# LED_POWER.net
KiCad netlist of a schematic drawn in Altium Designer
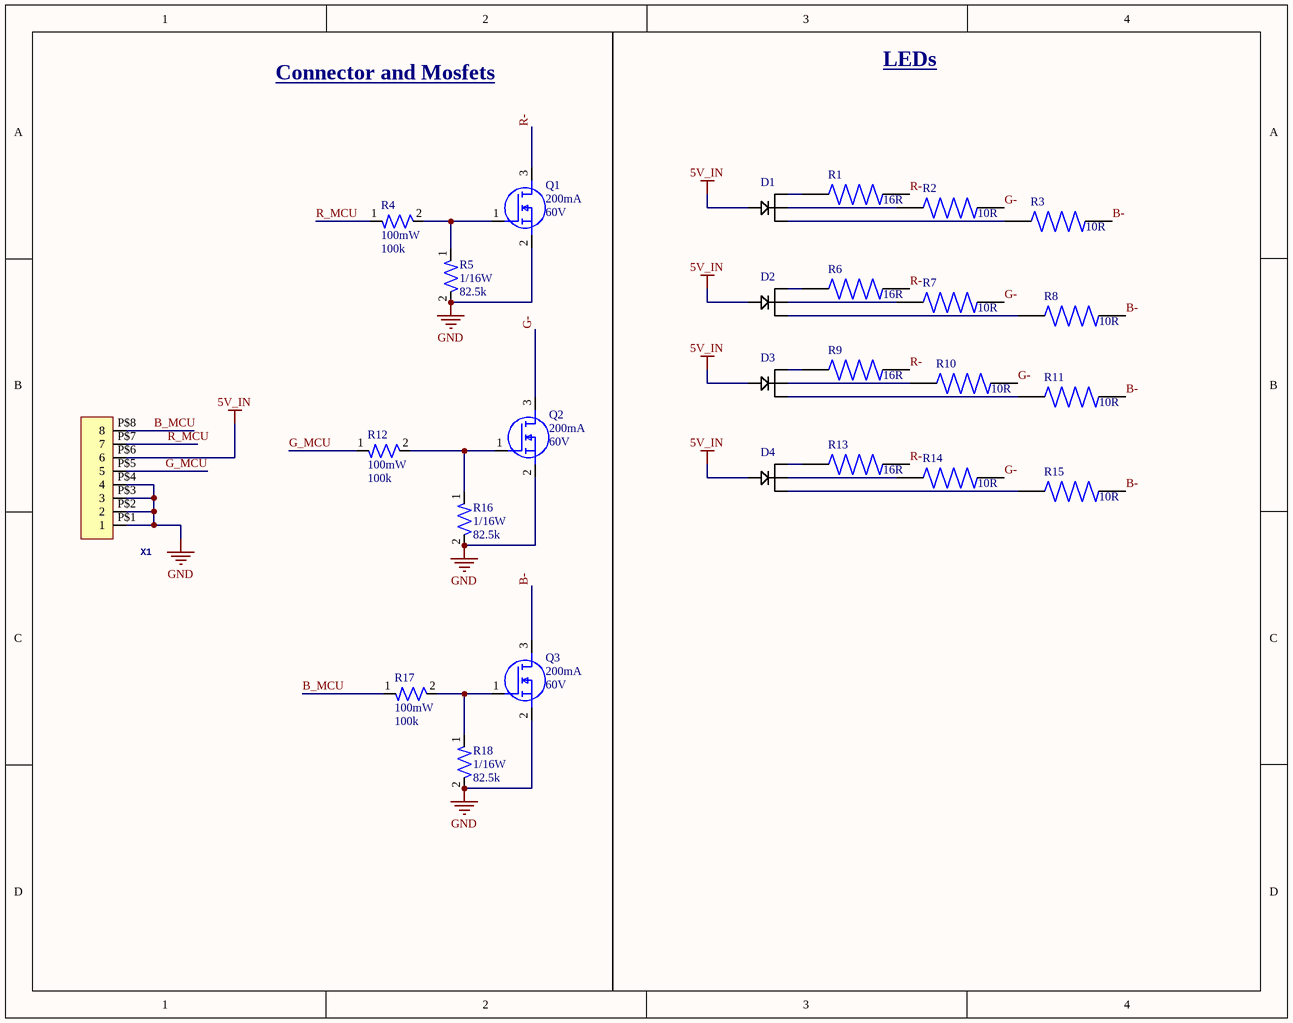
[diagram p0: LED_POWER.SchDoc]

(export (version "E")
  (design (tool "Eeschema 10.0.6"))
  (components
    (comp (ref "D1")
      (value "FD-9RGB-Y2")
      (footprint "RGBLED pcb")
      (description "https://www.adafruit.com/product/2524#technical-details")
      (libsource (lib "JLC_25") (part "3W-9W RGB LED"))
    )
    (comp (ref "D2")
      (value "FD-9RGB-Y2")
      (footprint "RGBLED pcb")
      (description "https://www.adafruit.com/product/2524#technical-details")
      (libsource (lib "JLC_25") (part "3W-9W RGB LED"))
    )
    (comp (ref "D3")
      (value "FD-9RGB-Y2")
      (footprint "RGBLED pcb")
      (description "https://www.adafruit.com/product/2524#technical-details")
      (libsource (lib "JLC_25") (part "3W-9W RGB LED"))
    )
    (comp (ref "D4")
      (value "FD-9RGB-Y2")
      (footprint "RGBLED pcb")
      (description "https://www.adafruit.com/product/2524#technical-details")
      (libsource (lib "JLC_25") (part "3W-9W RGB LED"))
    )
    (comp (ref "Q1")
      (value "T2N7002AK,LM")
      (footprint "IC-SOT23-3")
      (description "MOSFET N-CH 60V 200MA SOT23")
      (fields (field (name "CONTINUOUS CURRENT") "200mA") (field (name "VOLTAGE") "60V"))
      (libsource (lib "JLC_25") (part "NMOS-200MA-0001"))
    )
    (comp (ref "Q2")
      (value "T2N7002AK,LM")
      (footprint "IC-SOT23-3")
      (description "MOSFET N-CH 60V 200MA SOT23")
      (fields (field (name "CONTINUOUS CURRENT") "200mA") (field (name "VOLTAGE") "60V"))
      (libsource (lib "JLC_25") (part "NMOS-200MA-0001"))
    )
    (comp (ref "Q3")
      (value "T2N7002AK,LM")
      (footprint "IC-SOT23-3")
      (description "MOSFET N-CH 60V 200MA SOT23")
      (fields (field (name "CONTINUOUS CURRENT") "200mA") (field (name "VOLTAGE") "60V"))
      (libsource (lib "JLC_25") (part "NMOS-200MA-0001"))
    )
    (comp (ref "R1")
      (value "352116RFT")
      (footprint "RES-2512")
      (description "16 Ohms ±1% 2W Chip Resistor 2512 (6332 Metric) Automotive AEC-Q200, Moisture Resistant Thick Film")
      (fields (field (name "POWER") "2W") (field (name "RESISTANCE") "16R"))
      (libsource (lib "JLC_25") (part "RES-16-0001"))
    )
    (comp (ref "R2")
      (value "CRCW120610R0FKEAHP")
      (footprint "RES-1206")
      (fields (field (name "MF") "Vishay") (field (name "RESISTANCE") "10R") (field (name "POWER") "3/4W"))
      (libsource (lib "") (part "RES-10-0001_1"))
    )
    (comp (ref "R3")
      (value "CRCW120610R0FKEAHP")
      (footprint "RES-1206")
      (fields (field (name "MF") "Vishay") (field (name "RESISTANCE") "10R") (field (name "POWER") "3/4W"))
      (libsource (lib "JLC_25") (part "RES-10-0001"))
    )
    (comp (ref "R4")
      (value "RC0603FR-07100KL")
      (footprint "RES-0603")
      (description "RES SMD 100K OHM 1% 1/10W 0603")
      (fields
        (field (name "TOLERANCE") "1%")
        (field (name "POWER") "100mW")
        (field (name "RESISTANCE") "100k")
      )
      (libsource (lib "JLC_25") (part "RES-100k-0001"))
    )
    (comp (ref "R5")
      (value "RC0402FR-0782K5L")
      (footprint "RES-0402")
      (description "82.5 kOhms ±1% 0.063W, 1/16W Chip Resistor 0402 (1005 Metric) Moisture Resistant Thick Film")
      (fields
        (field (name "TOLERANCE") "1%")
        (field (name "POWER") "1/16W")
        (field (name "RESISTANCE") "82.5k")
      )
      (libsource (lib "JLC_25") (part "RES-82.5k-0001"))
    )
    (comp (ref "R6")
      (value "352116RFT")
      (footprint "RES-2512")
      (description "16 Ohms ±1% 2W Chip Resistor 2512 (6332 Metric) Automotive AEC-Q200, Moisture Resistant Thick Film")
      (fields (field (name "POWER") "2W") (field (name "RESISTANCE") "16R"))
      (libsource (lib "JLC_25") (part "RES-16-0001"))
    )
    (comp (ref "R7")
      (value "CRCW120610R0FKEAHP")
      (footprint "RES-1206")
      (fields (field (name "MF") "Vishay") (field (name "RESISTANCE") "10R") (field (name "POWER") "3/4W"))
      (libsource (lib "") (part "RES-10-0001_1"))
    )
    (comp (ref "R8")
      (value "CRCW120610R0FKEAHP")
      (footprint "RES-1206")
      (fields (field (name "MF") "Vishay") (field (name "RESISTANCE") "10R") (field (name "POWER") "3/4W"))
      (libsource (lib "JLC_25") (part "RES-10-0001"))
    )
    (comp (ref "R9")
      (value "352116RFT")
      (footprint "RES-2512")
      (description "16 Ohms ±1% 2W Chip Resistor 2512 (6332 Metric) Automotive AEC-Q200, Moisture Resistant Thick Film")
      (fields (field (name "POWER") "2W") (field (name "RESISTANCE") "16R"))
      (libsource (lib "JLC_25") (part "RES-16-0001"))
    )
    (comp (ref "R10")
      (value "CRCW120610R0FKEAHP")
      (footprint "RES-1206")
      (fields (field (name "MF") "Vishay") (field (name "RESISTANCE") "10R") (field (name "POWER") "3/4W"))
      (libsource (lib "") (part "RES-10-0001_1"))
    )
    (comp (ref "R11")
      (value "CRCW120610R0FKEAHP")
      (footprint "RES-1206")
      (fields (field (name "MF") "Vishay") (field (name "RESISTANCE") "10R") (field (name "POWER") "3/4W"))
      (libsource (lib "JLC_25") (part "RES-10-0001"))
    )
    (comp (ref "R12")
      (value "RC0603FR-07100KL")
      (footprint "RES-0603")
      (description "RES SMD 100K OHM 1% 1/10W 0603")
      (fields
        (field (name "TOLERANCE") "1%")
        (field (name "POWER") "100mW")
        (field (name "RESISTANCE") "100k")
      )
      (libsource (lib "JLC_25") (part "RES-100k-0001"))
    )
    (comp (ref "R13")
      (value "352116RFT")
      (footprint "RES-2512")
      (description "16 Ohms ±1% 2W Chip Resistor 2512 (6332 Metric) Automotive AEC-Q200, Moisture Resistant Thick Film")
      (fields (field (name "POWER") "2W") (field (name "RESISTANCE") "16R"))
      (libsource (lib "JLC_25") (part "RES-16-0001"))
    )
    (comp (ref "R14")
      (value "CRCW120610R0FKEAHP")
      (footprint "RES-1206")
      (fields (field (name "MF") "Vishay") (field (name "RESISTANCE") "10R") (field (name "POWER") "3/4W"))
      (libsource (lib "") (part "RES-10-0001_1"))
    )
    (comp (ref "R15")
      (value "CRCW120610R0FKEAHP")
      (footprint "RES-1206")
      (fields (field (name "MF") "Vishay") (field (name "RESISTANCE") "10R") (field (name "POWER") "3/4W"))
      (libsource (lib "JLC_25") (part "RES-10-0001"))
    )
    (comp (ref "R16")
      (value "RC0402FR-0782K5L")
      (footprint "RES-0402")
      (description "82.5 kOhms ±1% 0.063W, 1/16W Chip Resistor 0402 (1005 Metric) Moisture Resistant Thick Film")
      (fields
        (field (name "TOLERANCE") "1%")
        (field (name "POWER") "1/16W")
        (field (name "RESISTANCE") "82.5k")
      )
      (libsource (lib "JLC_25") (part "RES-82.5k-0001"))
    )
    (comp (ref "R17")
      (value "RC0603FR-07100KL")
      (footprint "RES-0603")
      (description "RES SMD 100K OHM 1% 1/10W 0603")
      (fields
        (field (name "TOLERANCE") "1%")
        (field (name "POWER") "100mW")
        (field (name "RESISTANCE") "100k")
      )
      (libsource (lib "JLC_25") (part "RES-100k-0001"))
    )
    (comp (ref "R18")
      (value "RC0402FR-0782K5L")
      (footprint "RES-0402")
      (description "82.5 kOhms ±1% 0.063W, 1/16W Chip Resistor 0402 (1005 Metric) Moisture Resistant Thick Film")
      (fields
        (field (name "TOLERANCE") "1%")
        (field (name "POWER") "1/16W")
        (field (name "RESISTANCE") "82.5k")
      )
      (libsource (lib "JLC_25") (part "RES-82.5k-0001"))
    )
    (comp (ref "X1")
      (value "Molex - Micro-Fit 3.0 Series connector,  3.00mm (0.118\") pitch header, 8 positions.")
      (footprint "43045-0800")
      (libsource (lib "Molex Microfit") (part "HEADER_POS8_?43045-0800"))
    )
  )
  (nets
    (net (code "1") (name "/B-") (class "Default")
      (node (ref "Q3") (pin "3") (pinfunction "D_3") (pintype "passive"))
      (node (ref "R11") (pin "2") (pinfunction "2_2") (pintype "passive"))
      (node (ref "R15") (pin "2") (pinfunction "2_2") (pintype "passive"))
      (node (ref "R3") (pin "2") (pinfunction "2_2") (pintype "passive"))
      (node (ref "R8") (pin "2") (pinfunction "2_2") (pintype "passive"))
    )
    (net (code "2") (name "/B_MCU") (class "Default")
      (node (ref "R17") (pin "1") (pinfunction "1_1") (pintype "passive"))
      (node (ref "X1") (pin "P$8") (pinfunction "8_P$8") (pintype "passive"))
    )
    (net (code "3") (name "/G-") (class "Default")
      (node (ref "Q2") (pin "3") (pinfunction "D_3") (pintype "passive"))
      (node (ref "R10") (pin "2") (pinfunction "2_2") (pintype "passive"))
      (node (ref "R14") (pin "2") (pinfunction "2_2") (pintype "passive"))
      (node (ref "R2") (pin "2") (pinfunction "2_2") (pintype "passive"))
      (node (ref "R7") (pin "2") (pinfunction "2_2") (pintype "passive"))
    )
    (net (code "4") (name "/G_MCU") (class "Default")
      (node (ref "R12") (pin "1") (pinfunction "1_1") (pintype "passive"))
      (node (ref "X1") (pin "P$5") (pinfunction "5_P$5") (pintype "passive"))
    )
    (net (code "5") (name "/R-") (class "Default")
      (node (ref "Q1") (pin "3") (pinfunction "D_3") (pintype "passive"))
      (node (ref "R1") (pin "2") (pinfunction "2_2") (pintype "passive"))
      (node (ref "R13") (pin "2") (pinfunction "2_2") (pintype "passive"))
      (node (ref "R6") (pin "2") (pinfunction "2_2") (pintype "passive"))
      (node (ref "R9") (pin "2") (pinfunction "2_2") (pintype "passive"))
    )
    (net (code "6") (name "/R_MCU") (class "Default")
      (node (ref "R4") (pin "1") (pinfunction "1_1") (pintype "passive"))
      (node (ref "X1") (pin "P$7") (pinfunction "7_P$7") (pintype "passive"))
    )
    (net (code "7") (name "5V_IN") (class "Default")
      (node (ref "D1") (pin "3") (pinfunction "B-_3") (pintype "passive"))
      (node (ref "D2") (pin "3") (pinfunction "B-_3") (pintype "passive"))
      (node (ref "D3") (pin "3") (pinfunction "B-_3") (pintype "passive"))
      (node (ref "D4") (pin "3") (pinfunction "B-_3") (pintype "passive"))
      (node (ref "X1") (pin "P$6") (pinfunction "6_P$6") (pintype "passive"))
    )
    (net (code "8") (name "GND") (class "Default")
      (node (ref "Q1") (pin "2") (pinfunction "S_2") (pintype "passive"))
      (node (ref "Q2") (pin "2") (pinfunction "S_2") (pintype "passive"))
      (node (ref "Q3") (pin "2") (pinfunction "S_2") (pintype "passive"))
      (node (ref "R16") (pin "2") (pinfunction "2_2") (pintype "passive"))
      (node (ref "R18") (pin "2") (pinfunction "2_2") (pintype "passive"))
      (node (ref "R5") (pin "2") (pinfunction "2_2") (pintype "passive"))
      (node (ref "X1") (pin "P$1") (pinfunction "1_P$1") (pintype "passive"))
      (node (ref "X1") (pin "P$2") (pinfunction "2_P$2") (pintype "passive"))
      (node (ref "X1") (pin "P$3") (pinfunction "3_P$3") (pintype "passive"))
      (node (ref "X1") (pin "P$4") (pinfunction "4_P$4") (pintype "passive"))
    )
    (net (code "9") (name "Net-(D1-7)") (class "Default")
      (node (ref "D1") (pin "0") (pinfunction "7_0") (pintype "passive"))
      (node (ref "R3") (pin "2") (pinfunction "2_2") (pintype "passive"))
    )
    (net (code "10") (name "Net-(D1-G-)") (class "Default")
      (node (ref "D1") (pin "2") (pinfunction "G-_2") (pintype "passive"))
      (node (ref "R2") (pin "1") (pinfunction "1_1") (pintype "passive"))
    )
    (net (code "11") (name "Net-(D1-R-)") (class "Default")
      (node (ref "D1") (pin "1") (pinfunction "R-_1") (pintype "passive"))
      (node (ref "R1") (pin "1") (pinfunction "1_1") (pintype "passive"))
    )
    (net (code "12") (name "Net-(D2-7)") (class "Default")
      (node (ref "D2") (pin "0") (pinfunction "7_0") (pintype "passive"))
      (node (ref "R8") (pin "2") (pinfunction "2_2") (pintype "passive"))
    )
    (net (code "13") (name "Net-(D2-G-)") (class "Default")
      (node (ref "D2") (pin "2") (pinfunction "G-_2") (pintype "passive"))
      (node (ref "R7") (pin "1") (pinfunction "1_1") (pintype "passive"))
    )
    (net (code "14") (name "Net-(D2-R-)") (class "Default")
      (node (ref "D2") (pin "1") (pinfunction "R-_1") (pintype "passive"))
      (node (ref "R6") (pin "1") (pinfunction "1_1") (pintype "passive"))
    )
    (net (code "15") (name "Net-(D3-7)") (class "Default")
      (node (ref "D3") (pin "0") (pinfunction "7_0") (pintype "passive"))
      (node (ref "R11") (pin "2") (pinfunction "2_2") (pintype "passive"))
    )
    (net (code "16") (name "Net-(D3-G-)") (class "Default")
      (node (ref "D3") (pin "2") (pinfunction "G-_2") (pintype "passive"))
      (node (ref "R10") (pin "1") (pinfunction "1_1") (pintype "passive"))
    )
    (net (code "17") (name "Net-(D3-R-)") (class "Default")
      (node (ref "D3") (pin "1") (pinfunction "R-_1") (pintype "passive"))
      (node (ref "R9") (pin "1") (pinfunction "1_1") (pintype "passive"))
    )
    (net (code "18") (name "Net-(D4-7)") (class "Default")
      (node (ref "D4") (pin "0") (pinfunction "7_0") (pintype "passive"))
      (node (ref "R15") (pin "2") (pinfunction "2_2") (pintype "passive"))
    )
    (net (code "19") (name "Net-(D4-G-)") (class "Default")
      (node (ref "D4") (pin "2") (pinfunction "G-_2") (pintype "passive"))
      (node (ref "R14") (pin "1") (pinfunction "1_1") (pintype "passive"))
    )
    (net (code "20") (name "Net-(D4-R-)") (class "Default")
      (node (ref "D4") (pin "1") (pinfunction "R-_1") (pintype "passive"))
      (node (ref "R13") (pin "1") (pinfunction "1_1") (pintype "passive"))
    )
    (net (code "21") (name "Net-(Q1-G)") (class "Default")
      (node (ref "Q1") (pin "1") (pinfunction "G_1") (pintype "passive"))
      (node (ref "R4") (pin "2") (pinfunction "2_2") (pintype "passive"))
      (node (ref "R5") (pin "1") (pinfunction "1_1") (pintype "passive"))
    )
    (net (code "22") (name "Net-(Q2-G)") (class "Default")
      (node (ref "Q2") (pin "1") (pinfunction "G_1") (pintype "passive"))
      (node (ref "R12") (pin "2") (pinfunction "2_2") (pintype "passive"))
      (node (ref "R16") (pin "1") (pinfunction "1_1") (pintype "passive"))
    )
    (net (code "23") (name "Net-(Q3-G)") (class "Default")
      (node (ref "Q3") (pin "1") (pinfunction "G_1") (pintype "passive"))
      (node (ref "R17") (pin "2") (pinfunction "2_2") (pintype "passive"))
      (node (ref "R18") (pin "1") (pinfunction "1_1") (pintype "passive"))
    )
  )
)
